# avrshift.net
KiCad netlist of a schematic drawn in EAGLE
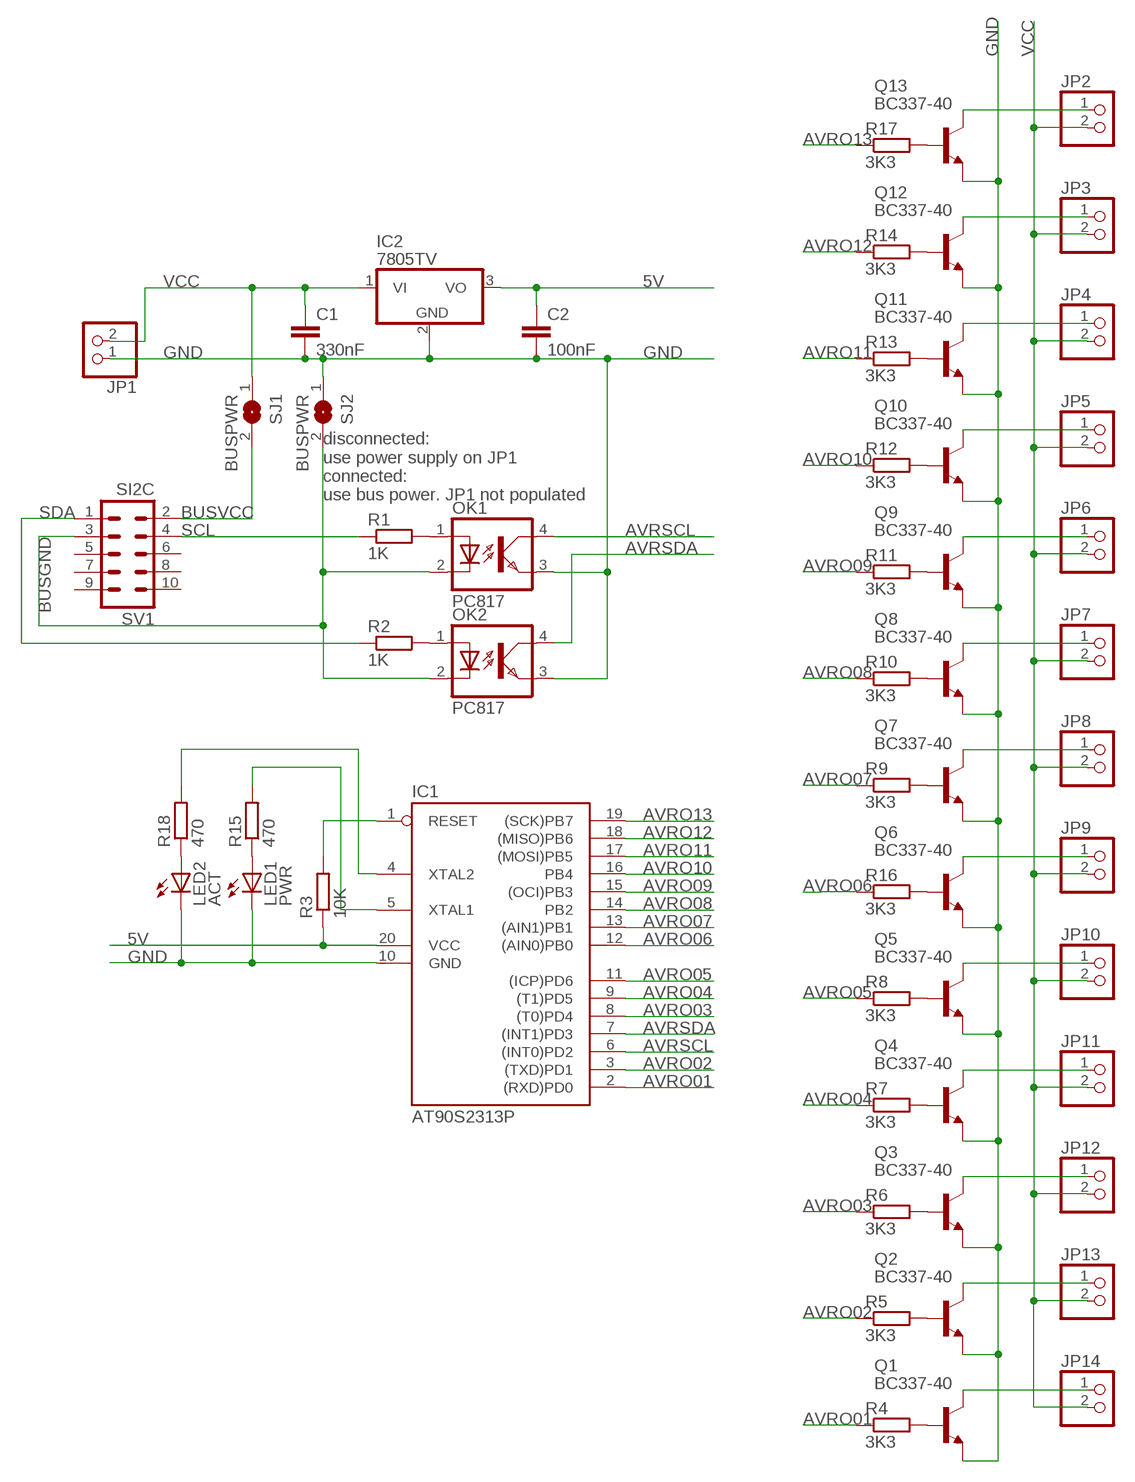
[diagram p0: schematic, sheet 1]

(export (version "E")
  (design (tool "Eeschema 10.0.6"))
  (components
    (comp (ref "C1")
      (value "330nF")
      (footprint "eagle-import:C2.5-3")
      (libsource (lib "eagle-import") (part "C2,5-3"))
    )
    (comp (ref "C2")
      (value "100nF")
      (footprint "eagle-import:C2.5-3")
      (libsource (lib "eagle-import") (part "C2,5-3"))
    )
    (comp (ref "IC1")
      (value "AT90S2313P")
      (footprint "eagle-import:DIL20")
      (libsource (lib "eagle-import") (part "AT90S2313P"))
    )
    (comp (ref "IC2")
      (value "7805TV")
      (footprint "eagle-import:TO220V")
      (libsource (lib "eagle-import") (part "78TV05"))
    )
    (comp (ref "JP1")
      (value "PINHD-1X2")
      (footprint "eagle-import:1X02")
      (libsource (lib "eagle-import") (part "PINHD-1X2"))
    )
    (comp (ref "JP2")
      (value "PINHD-1X2")
      (footprint "eagle-import:1X02")
      (libsource (lib "eagle-import") (part "PINHD-1X2"))
    )
    (comp (ref "JP3")
      (value "PINHD-1X2")
      (footprint "eagle-import:1X02")
      (libsource (lib "eagle-import") (part "PINHD-1X2"))
    )
    (comp (ref "JP4")
      (value "PINHD-1X2")
      (footprint "eagle-import:1X02")
      (libsource (lib "eagle-import") (part "PINHD-1X2"))
    )
    (comp (ref "JP5")
      (value "PINHD-1X2")
      (footprint "eagle-import:1X02")
      (libsource (lib "eagle-import") (part "PINHD-1X2"))
    )
    (comp (ref "JP6")
      (value "PINHD-1X2")
      (footprint "eagle-import:1X02")
      (libsource (lib "eagle-import") (part "PINHD-1X2"))
    )
    (comp (ref "JP7")
      (value "PINHD-1X2")
      (footprint "eagle-import:1X02")
      (libsource (lib "eagle-import") (part "PINHD-1X2"))
    )
    (comp (ref "JP8")
      (value "PINHD-1X2")
      (footprint "eagle-import:1X02")
      (libsource (lib "eagle-import") (part "PINHD-1X2"))
    )
    (comp (ref "JP9")
      (value "PINHD-1X2")
      (footprint "eagle-import:1X02")
      (libsource (lib "eagle-import") (part "PINHD-1X2"))
    )
    (comp (ref "JP10")
      (value "PINHD-1X2")
      (footprint "eagle-import:1X02")
      (libsource (lib "eagle-import") (part "PINHD-1X2"))
    )
    (comp (ref "JP11")
      (value "PINHD-1X2")
      (footprint "eagle-import:1X02")
      (libsource (lib "eagle-import") (part "PINHD-1X2"))
    )
    (comp (ref "JP12")
      (value "PINHD-1X2")
      (footprint "eagle-import:1X02")
      (libsource (lib "eagle-import") (part "PINHD-1X2"))
    )
    (comp (ref "JP13")
      (value "PINHD-1X2")
      (footprint "eagle-import:1X02")
      (libsource (lib "eagle-import") (part "PINHD-1X2"))
    )
    (comp (ref "JP14")
      (value "PINHD-1X2")
      (footprint "eagle-import:1X02")
      (libsource (lib "eagle-import") (part "PINHD-1X2"))
    )
    (comp (ref "LED1")
      (value "PWR")
      (footprint "eagle-import:LED3MM")
      (libsource (lib "eagle-import") (part "LED3MM"))
    )
    (comp (ref "LED2")
      (value "ACT")
      (footprint "eagle-import:LED3MM")
      (libsource (lib "eagle-import") (part "LED3MM"))
    )
    (comp (ref "OK1")
      (value "PC817")
      (footprint "eagle-import:DIL04")
      (fields (field (name "MPN") "PC817X4J000F"))
      (libsource (lib "eagle-import") (part "PC817"))
    )
    (comp (ref "OK2")
      (value "PC817")
      (footprint "eagle-import:DIL04")
      (fields (field (name "MPN") "PC817X4J000F"))
      (libsource (lib "eagle-import") (part "PC817"))
    )
    (comp (ref "Q1")
      (value "BC337-40")
      (footprint "eagle-import:TO92")
      (libsource (lib "eagle-import") (part "BC337-40"))
    )
    (comp (ref "Q2")
      (value "BC337-40")
      (footprint "eagle-import:TO92")
      (libsource (lib "eagle-import") (part "BC337-40"))
    )
    (comp (ref "Q3")
      (value "BC337-40")
      (footprint "eagle-import:TO92")
      (libsource (lib "eagle-import") (part "BC337-40"))
    )
    (comp (ref "Q4")
      (value "BC337-40")
      (footprint "eagle-import:TO92")
      (libsource (lib "eagle-import") (part "BC337-40"))
    )
    (comp (ref "Q5")
      (value "BC337-40")
      (footprint "eagle-import:TO92")
      (libsource (lib "eagle-import") (part "BC337-40"))
    )
    (comp (ref "Q6")
      (value "BC337-40")
      (footprint "eagle-import:TO92")
      (libsource (lib "eagle-import") (part "BC337-40"))
    )
    (comp (ref "Q7")
      (value "BC337-40")
      (footprint "eagle-import:TO92")
      (libsource (lib "eagle-import") (part "BC337-40"))
    )
    (comp (ref "Q8")
      (value "BC337-40")
      (footprint "eagle-import:TO92")
      (libsource (lib "eagle-import") (part "BC337-40"))
    )
    (comp (ref "Q9")
      (value "BC337-40")
      (footprint "eagle-import:TO92")
      (libsource (lib "eagle-import") (part "BC337-40"))
    )
    (comp (ref "Q10")
      (value "BC337-40")
      (footprint "eagle-import:TO92")
      (libsource (lib "eagle-import") (part "BC337-40"))
    )
    (comp (ref "Q11")
      (value "BC337-40")
      (footprint "eagle-import:TO92")
      (libsource (lib "eagle-import") (part "BC337-40"))
    )
    (comp (ref "Q12")
      (value "BC337-40")
      (footprint "eagle-import:TO92")
      (libsource (lib "eagle-import") (part "BC337-40"))
    )
    (comp (ref "Q13")
      (value "BC337-40")
      (footprint "eagle-import:TO92")
      (libsource (lib "eagle-import") (part "BC337-40"))
    )
    (comp (ref "R1")
      (value "1K")
      (footprint "eagle-import:0207_10")
      (libsource (lib "eagle-import") (part "R-EU_0207/10"))
    )
    (comp (ref "R2")
      (value "1K")
      (footprint "eagle-import:0207_10")
      (libsource (lib "eagle-import") (part "R-EU_0207/10"))
    )
    (comp (ref "R3")
      (value "10K")
      (footprint "eagle-import:0207_10")
      (libsource (lib "eagle-import") (part "R-EU_0207/10"))
    )
    (comp (ref "R4")
      (value "3K3")
      (footprint "eagle-import:0207_10")
      (libsource (lib "eagle-import") (part "R-EU_0207/10"))
    )
    (comp (ref "R5")
      (value "3K3")
      (footprint "eagle-import:0207_10")
      (libsource (lib "eagle-import") (part "R-EU_0207/10"))
    )
    (comp (ref "R6")
      (value "3K3")
      (footprint "eagle-import:0207_10")
      (libsource (lib "eagle-import") (part "R-EU_0207/10"))
    )
    (comp (ref "R7")
      (value "3K3")
      (footprint "eagle-import:0207_10")
      (libsource (lib "eagle-import") (part "R-EU_0207/10"))
    )
    (comp (ref "R8")
      (value "3K3")
      (footprint "eagle-import:0207_10")
      (libsource (lib "eagle-import") (part "R-EU_0207/10"))
    )
    (comp (ref "R9")
      (value "3K3")
      (footprint "eagle-import:0207_10")
      (libsource (lib "eagle-import") (part "R-EU_0207/10"))
    )
    (comp (ref "R10")
      (value "3K3")
      (footprint "eagle-import:0207_10")
      (libsource (lib "eagle-import") (part "R-EU_0207/10"))
    )
    (comp (ref "R11")
      (value "3K3")
      (footprint "eagle-import:0207_10")
      (libsource (lib "eagle-import") (part "R-EU_0207/10"))
    )
    (comp (ref "R12")
      (value "3K3")
      (footprint "eagle-import:0207_10")
      (libsource (lib "eagle-import") (part "R-EU_0207/10"))
    )
    (comp (ref "R13")
      (value "3K3")
      (footprint "eagle-import:0207_10")
      (libsource (lib "eagle-import") (part "R-EU_0207/10"))
    )
    (comp (ref "R14")
      (value "3K3")
      (footprint "eagle-import:0207_10")
      (libsource (lib "eagle-import") (part "R-EU_0207/10"))
    )
    (comp (ref "R15")
      (value "470")
      (footprint "eagle-import:0207_10")
      (libsource (lib "eagle-import") (part "R-EU_0207/10"))
    )
    (comp (ref "R16")
      (value "3K3")
      (footprint "eagle-import:0207_10")
      (libsource (lib "eagle-import") (part "R-EU_0207/10"))
    )
    (comp (ref "R17")
      (value "3K3")
      (footprint "eagle-import:0207_10")
      (libsource (lib "eagle-import") (part "R-EU_0207/10"))
    )
    (comp (ref "R18")
      (value "470")
      (footprint "eagle-import:0207_10")
      (libsource (lib "eagle-import") (part "R-EU_0207/10"))
    )
    (comp (ref "SJ1")
      (value "BUSPWR")
      (footprint "eagle-import:SJ")
      (libsource (lib "eagle-import") (part "SJ"))
    )
    (comp (ref "SJ2")
      (value "BUSPWR")
      (footprint "eagle-import:SJ")
      (libsource (lib "eagle-import") (part "SJ"))
    )
    (comp (ref "SV1")
      (value "SI2C")
      (footprint "eagle-import:ML10")
      (libsource (lib "eagle-import") (part "ML10"))
    )
  )
  (nets
    (net (code "1") (name "/5V") (class "Default")
      (node (ref "C2") (pin "1") (pinfunction "1_1") (pintype "passive"))
      (node (ref "IC1") (pin "20") (pinfunction "VCC_20") (pintype "power_in"))
      (node (ref "IC2") (pin "3") (pinfunction "VO_3") (pintype "passive"))
      (node (ref "R3") (pin "1") (pinfunction "1_1") (pintype "passive"))
    )
    (net (code "2") (name "/AVRO01") (class "Default")
      (node (ref "IC1") (pin "2") (pinfunction "(RXD)PD0_2") (pintype "bidirectional"))
      (node (ref "R4") (pin "1") (pinfunction "1_1") (pintype "passive"))
    )
    (net (code "3") (name "/AVRO02") (class "Default")
      (node (ref "IC1") (pin "3") (pinfunction "(TXD)PD1_3") (pintype "bidirectional"))
      (node (ref "R5") (pin "1") (pinfunction "1_1") (pintype "passive"))
    )
    (net (code "4") (name "/AVRO03") (class "Default")
      (node (ref "IC1") (pin "8") (pinfunction "(T0)PD4_8") (pintype "bidirectional"))
      (node (ref "R6") (pin "1") (pinfunction "1_1") (pintype "passive"))
    )
    (net (code "5") (name "/AVRO04") (class "Default")
      (node (ref "IC1") (pin "9") (pinfunction "(T1)PD5_9") (pintype "bidirectional"))
      (node (ref "R7") (pin "1") (pinfunction "1_1") (pintype "passive"))
    )
    (net (code "6") (name "/AVRO05") (class "Default")
      (node (ref "IC1") (pin "11") (pinfunction "(ICP)PD6_11") (pintype "bidirectional"))
      (node (ref "R8") (pin "1") (pinfunction "1_1") (pintype "passive"))
    )
    (net (code "7") (name "/AVRO06") (class "Default")
      (node (ref "IC1") (pin "12") (pinfunction "(AIN0)PB0_12") (pintype "bidirectional"))
      (node (ref "R16") (pin "1") (pinfunction "1_1") (pintype "passive"))
    )
    (net (code "8") (name "/AVRO07") (class "Default")
      (node (ref "IC1") (pin "13") (pinfunction "(AIN1)PB1_13") (pintype "bidirectional"))
      (node (ref "R9") (pin "1") (pinfunction "1_1") (pintype "passive"))
    )
    (net (code "9") (name "/AVRO08") (class "Default")
      (node (ref "IC1") (pin "14") (pinfunction "PB2_14") (pintype "bidirectional"))
      (node (ref "R10") (pin "1") (pinfunction "1_1") (pintype "passive"))
    )
    (net (code "10") (name "/AVRO09") (class "Default")
      (node (ref "IC1") (pin "15") (pinfunction "(OCI)PB3_15") (pintype "bidirectional"))
      (node (ref "R11") (pin "1") (pinfunction "1_1") (pintype "passive"))
    )
    (net (code "11") (name "/AVRO10") (class "Default")
      (node (ref "IC1") (pin "16") (pinfunction "PB4_16") (pintype "bidirectional"))
      (node (ref "R12") (pin "1") (pinfunction "1_1") (pintype "passive"))
    )
    (net (code "12") (name "/AVRO11") (class "Default")
      (node (ref "IC1") (pin "17") (pinfunction "(MOSI)PB5_17") (pintype "bidirectional"))
      (node (ref "R13") (pin "1") (pinfunction "1_1") (pintype "passive"))
    )
    (net (code "13") (name "/AVRO12") (class "Default")
      (node (ref "IC1") (pin "18") (pinfunction "(MISO)PB6_18") (pintype "bidirectional"))
      (node (ref "R14") (pin "1") (pinfunction "1_1") (pintype "passive"))
    )
    (net (code "14") (name "/AVRO13") (class "Default")
      (node (ref "IC1") (pin "19") (pinfunction "(SCK)PB7_19") (pintype "bidirectional"))
      (node (ref "R17") (pin "1") (pinfunction "1_1") (pintype "passive"))
    )
    (net (code "15") (name "/AVRSCL") (class "Default")
      (node (ref "IC1") (pin "6") (pinfunction "(INT0)PD2_6") (pintype "bidirectional"))
      (node (ref "OK1") (pin "4") (pinfunction "COL_4") (pintype "passive"))
    )
    (net (code "16") (name "/AVRSDA") (class "Default")
      (node (ref "IC1") (pin "7") (pinfunction "(INT1)PD3_7") (pintype "bidirectional"))
      (node (ref "OK2") (pin "4") (pinfunction "COL_4") (pintype "passive"))
    )
    (net (code "17") (name "/BUSGND") (class "Default")
      (node (ref "OK1") (pin "2") (pinfunction "C_2") (pintype "passive"))
      (node (ref "OK2") (pin "2") (pinfunction "C_2") (pintype "passive"))
      (node (ref "SJ2") (pin "2") (pinfunction "2_2") (pintype "passive"))
      (node (ref "SV1") (pin "3") (pinfunction "3_3") (pintype "passive"))
    )
    (net (code "18") (name "/BUSVCC") (class "Default")
      (node (ref "SJ1") (pin "2") (pinfunction "2_2") (pintype "passive"))
      (node (ref "SV1") (pin "2") (pinfunction "2_2") (pintype "passive"))
    )
    (net (code "19") (name "/GND") (class "Default")
      (node (ref "C1") (pin "2") (pinfunction "2_2") (pintype "passive"))
      (node (ref "C2") (pin "2") (pinfunction "2_2") (pintype "passive"))
      (node (ref "IC1") (pin "10") (pinfunction "GND_10") (pintype "power_in"))
      (node (ref "IC2") (pin "2") (pinfunction "GND_2") (pintype "passive"))
      (node (ref "JP1") (pin "1") (pinfunction "1_1") (pintype "passive"))
      (node (ref "LED1") (pin "K") (pinfunction "C_K") (pintype "passive"))
      (node (ref "LED2") (pin "K") (pinfunction "C_K") (pintype "passive"))
      (node (ref "OK1") (pin "3") (pinfunction "EMIT_3") (pintype "passive"))
      (node (ref "OK2") (pin "3") (pinfunction "EMIT_3") (pintype "passive"))
      (node (ref "Q1") (pin "1") (pinfunction "E_1") (pintype "passive"))
      (node (ref "Q10") (pin "1") (pinfunction "E_1") (pintype "passive"))
      (node (ref "Q11") (pin "1") (pinfunction "E_1") (pintype "passive"))
      (node (ref "Q12") (pin "1") (pinfunction "E_1") (pintype "passive"))
      (node (ref "Q13") (pin "1") (pinfunction "E_1") (pintype "passive"))
      (node (ref "Q2") (pin "1") (pinfunction "E_1") (pintype "passive"))
      (node (ref "Q3") (pin "1") (pinfunction "E_1") (pintype "passive"))
      (node (ref "Q4") (pin "1") (pinfunction "E_1") (pintype "passive"))
      (node (ref "Q5") (pin "1") (pinfunction "E_1") (pintype "passive"))
      (node (ref "Q6") (pin "1") (pinfunction "E_1") (pintype "passive"))
      (node (ref "Q7") (pin "1") (pinfunction "E_1") (pintype "passive"))
      (node (ref "Q8") (pin "1") (pinfunction "E_1") (pintype "passive"))
      (node (ref "Q9") (pin "1") (pinfunction "E_1") (pintype "passive"))
      (node (ref "SJ2") (pin "1") (pinfunction "1_1") (pintype "passive"))
    )
    (net (code "20") (name "/SCL") (class "Default")
      (node (ref "R1") (pin "1") (pinfunction "1_1") (pintype "passive"))
      (node (ref "SV1") (pin "4") (pinfunction "4_4") (pintype "passive"))
    )
    (net (code "21") (name "/SDA") (class "Default")
      (node (ref "R2") (pin "1") (pinfunction "1_1") (pintype "passive"))
      (node (ref "SV1") (pin "1") (pinfunction "1_1") (pintype "passive"))
    )
    (net (code "22") (name "/VCC") (class "Default")
      (node (ref "C1") (pin "1") (pinfunction "1_1") (pintype "passive"))
      (node (ref "IC2") (pin "1") (pinfunction "VI_1") (pintype "input"))
      (node (ref "JP1") (pin "2") (pinfunction "2_2") (pintype "passive"))
      (node (ref "JP10") (pin "2") (pinfunction "2_2") (pintype "passive"))
      (node (ref "JP11") (pin "2") (pinfunction "2_2") (pintype "passive"))
      (node (ref "JP12") (pin "2") (pinfunction "2_2") (pintype "passive"))
      (node (ref "JP13") (pin "2") (pinfunction "2_2") (pintype "passive"))
      (node (ref "JP14") (pin "2") (pinfunction "2_2") (pintype "passive"))
      (node (ref "JP2") (pin "2") (pinfunction "2_2") (pintype "passive"))
      (node (ref "JP3") (pin "2") (pinfunction "2_2") (pintype "passive"))
      (node (ref "JP4") (pin "2") (pinfunction "2_2") (pintype "passive"))
      (node (ref "JP5") (pin "2") (pinfunction "2_2") (pintype "passive"))
      (node (ref "JP6") (pin "2") (pinfunction "2_2") (pintype "passive"))
      (node (ref "JP7") (pin "2") (pinfunction "2_2") (pintype "passive"))
      (node (ref "JP8") (pin "2") (pinfunction "2_2") (pintype "passive"))
      (node (ref "JP9") (pin "2") (pinfunction "2_2") (pintype "passive"))
      (node (ref "SJ1") (pin "1") (pinfunction "1_1") (pintype "passive"))
    )
    (net (code "23") (name "Net-(IC1-RESET)") (class "Default")
      (node (ref "IC1") (pin "1") (pinfunction "RESET_1") (pintype "bidirectional"))
      (node (ref "R3") (pin "2") (pinfunction "2_2") (pintype "passive"))
    )
    (net (code "24") (name "Net-(IC1-XTAL1)") (class "Default")
      (node (ref "IC1") (pin "5") (pinfunction "XTAL1_5") (pintype "bidirectional"))
      (node (ref "R15") (pin "2") (pinfunction "2_2") (pintype "passive"))
    )
    (net (code "25") (name "Net-(IC1-XTAL2)") (class "Default")
      (node (ref "IC1") (pin "4") (pinfunction "XTAL2_4") (pintype "bidirectional"))
      (node (ref "R18") (pin "2") (pinfunction "2_2") (pintype "passive"))
    )
    (net (code "26") (name "Net-(LED1-PadA)") (class "Default")
      (node (ref "LED1") (pin "A") (pinfunction "A_A") (pintype "passive"))
      (node (ref "R15") (pin "1") (pinfunction "1_1") (pintype "passive"))
    )
    (net (code "27") (name "Net-(LED2-PadA)") (class "Default")
      (node (ref "LED2") (pin "A") (pinfunction "A_A") (pintype "passive"))
      (node (ref "R18") (pin "1") (pinfunction "1_1") (pintype "passive"))
    )
    (net (code "28") (name "Net-(OK1-A)") (class "Default")
      (node (ref "OK1") (pin "1") (pinfunction "A_1") (pintype "passive"))
      (node (ref "R1") (pin "2") (pinfunction "2_2") (pintype "passive"))
    )
    (net (code "29") (name "Net-(OK2-A)") (class "Default")
      (node (ref "OK2") (pin "1") (pinfunction "A_1") (pintype "passive"))
      (node (ref "R2") (pin "2") (pinfunction "2_2") (pintype "passive"))
    )
    (net (code "30") (name "Net-(Q1-B)") (class "Default")
      (node (ref "Q1") (pin "2") (pinfunction "B_2") (pintype "passive"))
      (node (ref "R4") (pin "2") (pinfunction "2_2") (pintype "passive"))
    )
    (net (code "31") (name "Net-(Q1-C)") (class "Default")
      (node (ref "JP14") (pin "1") (pinfunction "1_1") (pintype "passive"))
      (node (ref "Q1") (pin "3") (pinfunction "C_3") (pintype "passive"))
    )
    (net (code "32") (name "Net-(Q2-B)") (class "Default")
      (node (ref "Q2") (pin "2") (pinfunction "B_2") (pintype "passive"))
      (node (ref "R5") (pin "2") (pinfunction "2_2") (pintype "passive"))
    )
    (net (code "33") (name "Net-(Q2-C)") (class "Default")
      (node (ref "JP13") (pin "1") (pinfunction "1_1") (pintype "passive"))
      (node (ref "Q2") (pin "3") (pinfunction "C_3") (pintype "passive"))
    )
    (net (code "34") (name "Net-(Q3-B)") (class "Default")
      (node (ref "Q3") (pin "2") (pinfunction "B_2") (pintype "passive"))
      (node (ref "R6") (pin "2") (pinfunction "2_2") (pintype "passive"))
    )
    (net (code "35") (name "Net-(Q3-C)") (class "Default")
      (node (ref "JP12") (pin "1") (pinfunction "1_1") (pintype "passive"))
      (node (ref "Q3") (pin "3") (pinfunction "C_3") (pintype "passive"))
    )
    (net (code "36") (name "Net-(Q4-B)") (class "Default")
      (node (ref "Q4") (pin "2") (pinfunction "B_2") (pintype "passive"))
      (node (ref "R7") (pin "2") (pinfunction "2_2") (pintype "passive"))
    )
    (net (code "37") (name "Net-(Q4-C)") (class "Default")
      (node (ref "JP11") (pin "1") (pinfunction "1_1") (pintype "passive"))
      (node (ref "Q4") (pin "3") (pinfunction "C_3") (pintype "passive"))
    )
    (net (code "38") (name "Net-(Q5-B)") (class "Default")
      (node (ref "Q5") (pin "2") (pinfunction "B_2") (pintype "passive"))
      (node (ref "R8") (pin "2") (pinfunction "2_2") (pintype "passive"))
    )
    (net (code "39") (name "Net-(Q5-C)") (class "Default")
      (node (ref "JP10") (pin "1") (pinfunction "1_1") (pintype "passive"))
      (node (ref "Q5") (pin "3") (pinfunction "C_3") (pintype "passive"))
    )
    (net (code "40") (name "Net-(Q6-B)") (class "Default")
      (node (ref "Q6") (pin "2") (pinfunction "B_2") (pintype "passive"))
      (node (ref "R16") (pin "2") (pinfunction "2_2") (pintype "passive"))
    )
    (net (code "41") (name "Net-(Q6-C)") (class "Default")
      (node (ref "JP9") (pin "1") (pinfunction "1_1") (pintype "passive"))
      (node (ref "Q6") (pin "3") (pinfunction "C_3") (pintype "passive"))
    )
    (net (code "42") (name "Net-(Q7-B)") (class "Default")
      (node (ref "Q7") (pin "2") (pinfunction "B_2") (pintype "passive"))
      (node (ref "R9") (pin "2") (pinfunction "2_2") (pintype "passive"))
    )
    (net (code "43") (name "Net-(Q7-C)") (class "Default")
      (node (ref "JP8") (pin "1") (pinfunction "1_1") (pintype "passive"))
      (node (ref "Q7") (pin "3") (pinfunction "C_3") (pintype "passive"))
    )
    (net (code "44") (name "Net-(Q8-B)") (class "Default")
      (node (ref "Q8") (pin "2") (pinfunction "B_2") (pintype "passive"))
      (node (ref "R10") (pin "2") (pinfunction "2_2") (pintype "passive"))
    )
    (net (code "45") (name "Net-(Q8-C)") (class "Default")
      (node (ref "JP7") (pin "1") (pinfunction "1_1") (pintype "passive"))
      (node (ref "Q8") (pin "3") (pinfunction "C_3") (pintype "passive"))
    )
    (net (code "46") (name "Net-(Q9-B)") (class "Default")
      (node (ref "Q9") (pin "2") (pinfunction "B_2") (pintype "passive"))
      (node (ref "R11") (pin "2") (pinfunction "2_2") (pintype "passive"))
    )
    (net (code "47") (name "Net-(Q9-C)") (class "Default")
      (node (ref "JP6") (pin "1") (pinfunction "1_1") (pintype "passive"))
      (node (ref "Q9") (pin "3") (pinfunction "C_3") (pintype "passive"))
    )
    (net (code "48") (name "Net-(Q10-B)") (class "Default")
      (node (ref "Q10") (pin "2") (pinfunction "B_2") (pintype "passive"))
      (node (ref "R12") (pin "2") (pinfunction "2_2") (pintype "passive"))
    )
    (net (code "49") (name "Net-(Q10-C)") (class "Default")
      (node (ref "JP5") (pin "1") (pinfunction "1_1") (pintype "passive"))
      (node (ref "Q10") (pin "3") (pinfunction "C_3") (pintype "passive"))
    )
    (net (code "50") (name "Net-(Q11-B)") (class "Default")
      (node (ref "Q11") (pin "2") (pinfunction "B_2") (pintype "passive"))
      (node (ref "R13") (pin "2") (pinfunction "2_2") (pintype "passive"))
    )
    (net (code "51") (name "Net-(Q11-C)") (class "Default")
      (node (ref "JP4") (pin "1") (pinfunction "1_1") (pintype "passive"))
      (node (ref "Q11") (pin "3") (pinfunction "C_3") (pintype "passive"))
    )
    (net (code "52") (name "Net-(Q12-B)") (class "Default")
      (node (ref "Q12") (pin "2") (pinfunction "B_2") (pintype "passive"))
      (node (ref "R14") (pin "2") (pinfunction "2_2") (pintype "passive"))
    )
    (net (code "53") (name "Net-(Q12-C)") (class "Default")
      (node (ref "JP3") (pin "1") (pinfunction "1_1") (pintype "passive"))
      (node (ref "Q12") (pin "3") (pinfunction "C_3") (pintype "passive"))
    )
    (net (code "54") (name "Net-(Q13-B)") (class "Default")
      (node (ref "Q13") (pin "2") (pinfunction "B_2") (pintype "passive"))
      (node (ref "R17") (pin "2") (pinfunction "2_2") (pintype "passive"))
    )
    (net (code "55") (name "Net-(Q13-C)") (class "Default")
      (node (ref "JP2") (pin "1") (pinfunction "1_1") (pintype "passive"))
      (node (ref "Q13") (pin "3") (pinfunction "C_3") (pintype "passive"))
    )
    (net (code "56") (name "unconnected-(SV1-Pad5)") (class "Default")
      (node (ref "SV1") (pin "5") (pinfunction "5_5") (pintype "passive"))
    )
    (net (code "57") (name "unconnected-(SV1-Pad6)") (class "Default")
      (node (ref "SV1") (pin "6") (pinfunction "6_6") (pintype "passive"))
    )
    (net (code "58") (name "unconnected-(SV1-Pad7)") (class "Default")
      (node (ref "SV1") (pin "7") (pinfunction "7_7") (pintype "passive"))
    )
    (net (code "59") (name "unconnected-(SV1-Pad8)") (class "Default")
      (node (ref "SV1") (pin "8") (pinfunction "8_8") (pintype "passive"))
    )
    (net (code "60") (name "unconnected-(SV1-Pad9)") (class "Default")
      (node (ref "SV1") (pin "9") (pinfunction "9_9") (pintype "passive"))
    )
    (net (code "61") (name "unconnected-(SV1-Pad10)") (class "Default")
      (node (ref "SV1") (pin "10") (pinfunction "10_10") (pintype "passive"))
    )
  )
)
